# Thermocouple_interface.net
KiCad netlist of a schematic drawn in Altium Designer
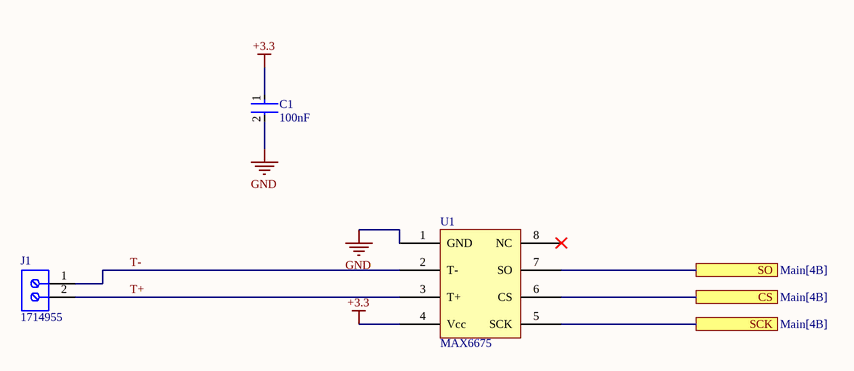
[diagram p0: Thermocouple_interface.SchDoc]

(export (version "E")
  (design (tool "Eeschema 10.0.6"))
  (components
    (comp (ref "C1")
      (value "100nF")
      (footprint "FP-0805-L_2_01_0_2-W_1_25-IPC_B")
      (description "General Purpose Ceramic Capacitor, 0805, 100nF, 10%, X7R, 15%, 100V")
      (fields (field (name "VOLTAGE") "100V") (field (name "TOLERANCE") "10%"))
      (libsource (lib "Altium Content Vault") (part "b4654b650e69147ec39a6b967a45e02"))
    )
    (comp (ref "J1")
      (value "1714955")
      (footprint "PHOE-1714955_V")
      (description "PC Terminal Block, Pitch 6.35 mm, 1 x 2 Position, Height 21.5 mm, Tail Lenght 5.1 mm, RoHS, Bulk")
      (fields (field (name "MANUFACTURER") "Phoenix Contact"))
      (libsource (lib "Altium Content Vault") (part "CN-1P-F-TB2"))
    )
    (comp (ref "U1")
      (value "MAX6675")
      (footprint "SO08")
      (libsource (lib "Schematic_library") (part "MAX6675"))
    )
  )
  (nets
    (net (code "1") (name "+3.3") (class "Default")
      (node (ref "C1") (pin "1") (pinfunction "1_1") (pintype "passive"))
      (node (ref "U1") (pin "4") (pinfunction "Vcc_4") (pintype "passive"))
    )
    (net (code "2") (name "/CS") (class "Default")
      (node (ref "U1") (pin "6") (pinfunction "CS_6") (pintype "passive"))
    )
    (net (code "3") (name "/SCK") (class "Default")
      (node (ref "U1") (pin "5") (pinfunction "SCK_5") (pintype "passive"))
    )
    (net (code "4") (name "/SO") (class "Default")
      (node (ref "U1") (pin "7") (pinfunction "SO_7") (pintype "passive"))
    )
    (net (code "5") (name "/T+") (class "Default")
      (node (ref "J1") (pin "2") (pinfunction "2_2") (pintype "passive"))
      (node (ref "U1") (pin "3") (pinfunction "T+_3") (pintype "passive"))
    )
    (net (code "6") (name "/T-") (class "Default")
      (node (ref "J1") (pin "1") (pinfunction "1_1") (pintype "passive"))
      (node (ref "U1") (pin "2") (pinfunction "T-_2") (pintype "passive"))
    )
    (net (code "7") (name "GND") (class "Default")
      (node (ref "C1") (pin "2") (pinfunction "2_2") (pintype "passive"))
      (node (ref "U1") (pin "1") (pinfunction "GND_1") (pintype "passive"))
    )
    (net (code "8") (name "unconnected-(U1-NC-Pad8)") (class "Default")
      (node (ref "U1") (pin "8") (pinfunction "NC_8") (pintype "passive+no_connect"))
    )
  )
)
